# MinipHV0_1.net
KiCad netlist of a schematic drawn in EAGLE
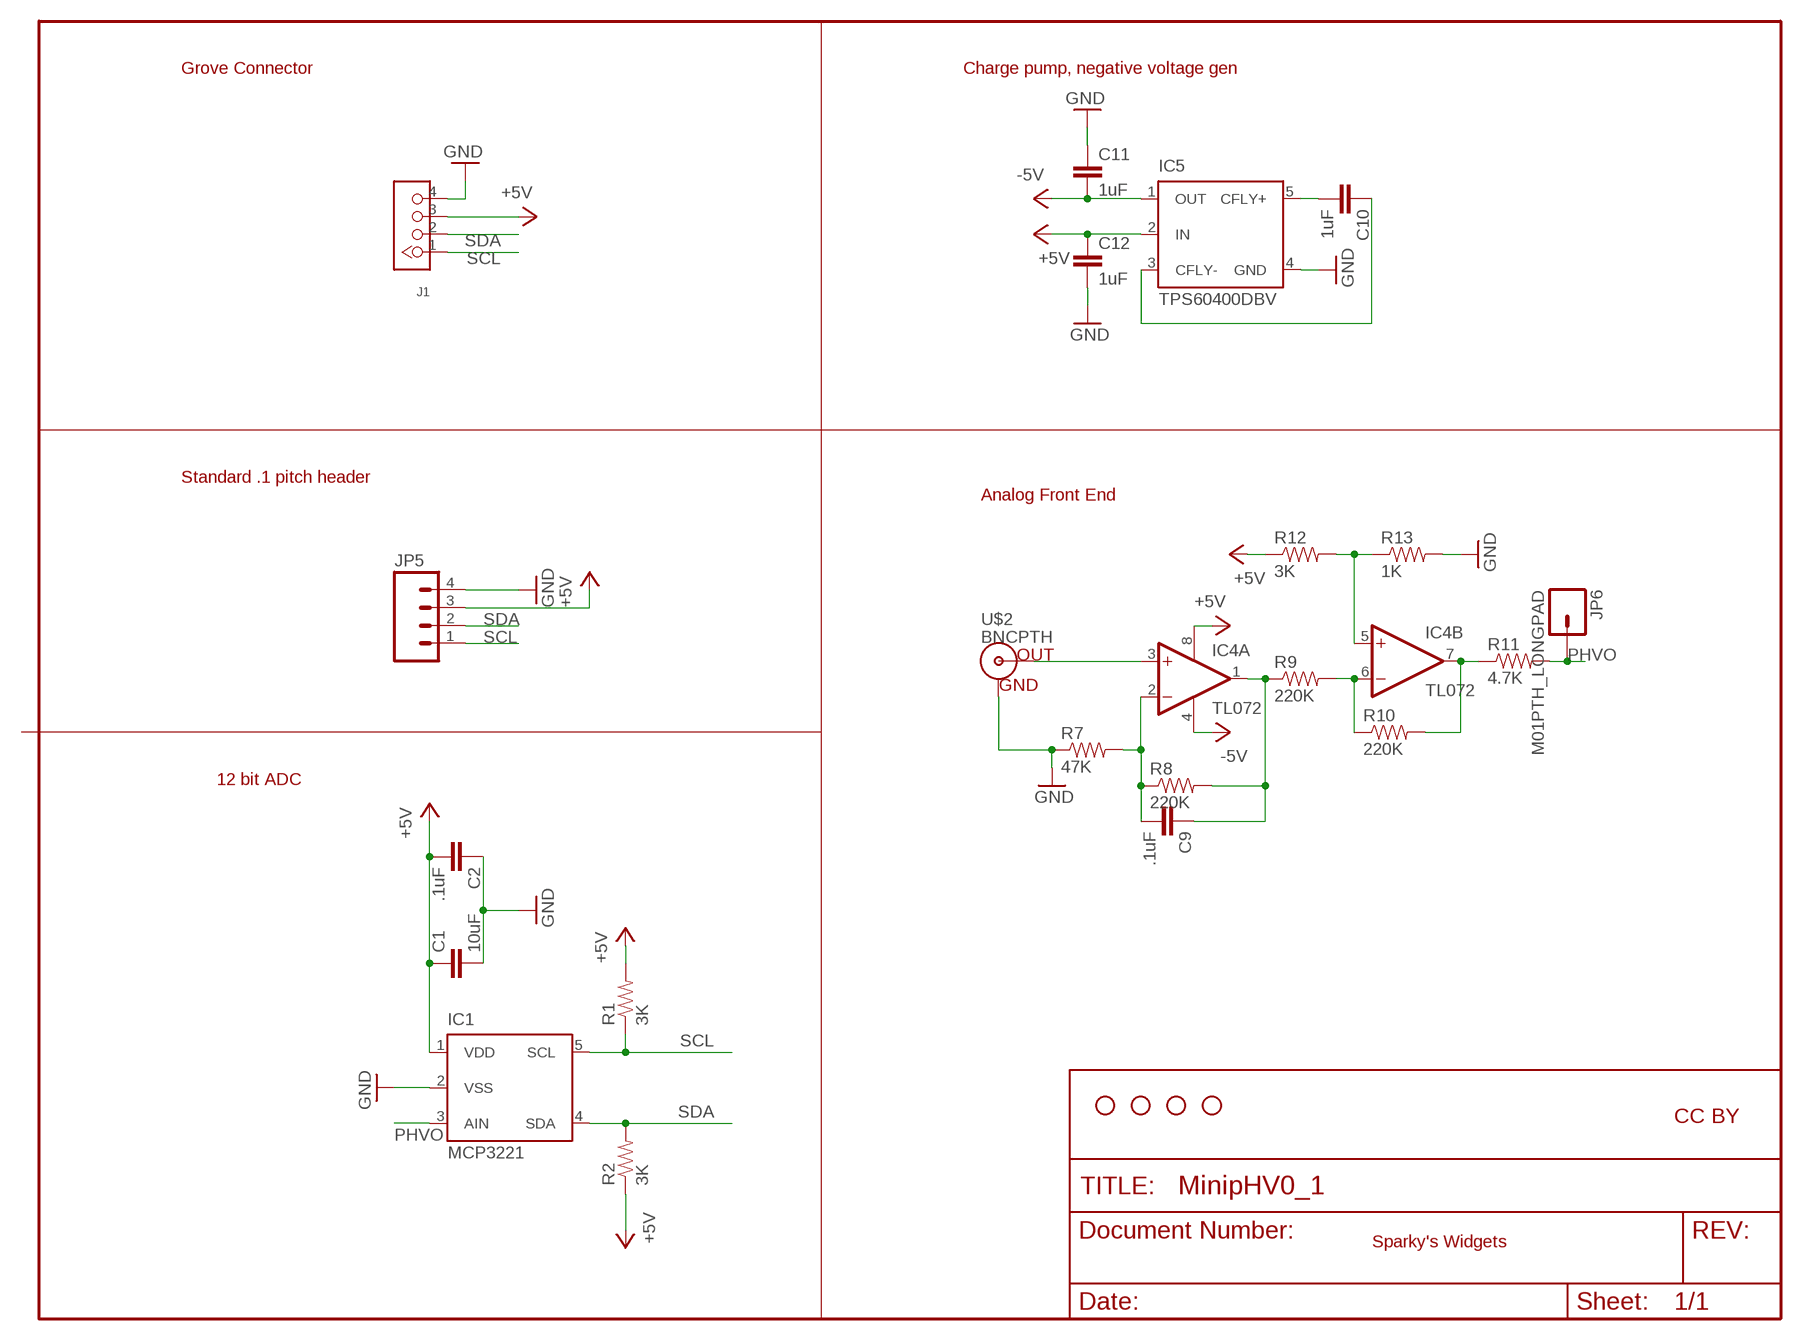
[diagram p0: schematic, sheet 1]

(export (version "E")
  (design (tool "Eeschema 10.0.6"))
  (components
    (comp (ref "C1")
      (value "10uF")
      (footprint "eagle-import:0805")
      (libsource (lib "eagle-import") (part "CAP0805"))
    )
    (comp (ref "C2")
      (value ".1uF")
      (footprint "eagle-import:0805")
      (libsource (lib "eagle-import") (part "CAP0805"))
    )
    (comp (ref "C9")
      (value ".1uF")
      (footprint "eagle-import:0805")
      (libsource (lib "eagle-import") (part "CAP0805"))
    )
    (comp (ref "C10")
      (value "1uF")
      (footprint "eagle-import:0805")
      (libsource (lib "eagle-import") (part "CAP0805"))
    )
    (comp (ref "C11")
      (value "1uF")
      (footprint "eagle-import:0805")
      (libsource (lib "eagle-import") (part "CAP0805"))
    )
    (comp (ref "C12")
      (value "1uF")
      (footprint "eagle-import:0805")
      (libsource (lib "eagle-import") (part "CAP0805"))
    )
    (comp (ref "IC1")
      (value "MCP3221")
      (footprint "eagle-import:SOT23-DBV")
      (libsource (lib "eagle-import") (part "MCP3221"))
    )
    (comp (ref "IC4")
      (value "TL072")
      (footprint "eagle-import:SO08")
      (libsource (lib "eagle-import") (part "LM358D"))
    )
    (comp (ref "IC5")
      (value "TPS60400DBV")
      (footprint "eagle-import:SOT23-DBV")
      (libsource (lib "eagle-import") (part "TPS60400DBV"))
    )
    (comp (ref "J1")
      (value "TWIG-4P-2.0-2.0")
      (footprint "eagle-import:4P-2.0")
      (libsource (lib "eagle-import") (part "TWIG-4P-2.0-2.0"))
    )
    (comp (ref "JP1")
      (value "STAND-OFF")
      (footprint "eagle-import:STAND-OFF")
      (libsource (lib "eagle-import") (part "STAND-OFF"))
    )
    (comp (ref "JP2")
      (value "STAND-OFF")
      (footprint "eagle-import:STAND-OFF")
      (libsource (lib "eagle-import") (part "STAND-OFF"))
    )
    (comp (ref "JP3")
      (value "STAND-OFF")
      (footprint "eagle-import:STAND-OFF")
      (libsource (lib "eagle-import") (part "STAND-OFF"))
    )
    (comp (ref "JP4")
      (value "STAND-OFF")
      (footprint "eagle-import:STAND-OFF")
      (libsource (lib "eagle-import") (part "STAND-OFF"))
    )
    (comp (ref "JP5")
      (value "M04PTH")
      (footprint "eagle-import:1X04")
      (libsource (lib "eagle-import") (part "M04PTH"))
    )
    (comp (ref "JP6")
      (value "M01PTH_LONGPAD")
      (footprint "eagle-import:1X01_LONGPAD")
      (libsource (lib "eagle-import") (part "M01PTH_LONGPAD"))
    )
    (comp (ref "R1")
      (value "3K")
      (footprint "eagle-import:0805")
      (libsource (lib "eagle-import") (part "RESISTOR0805-RES"))
    )
    (comp (ref "R2")
      (value "3K")
      (footprint "eagle-import:0805")
      (libsource (lib "eagle-import") (part "RESISTOR0805-RES"))
    )
    (comp (ref "R7")
      (value "47K")
      (footprint "eagle-import:0805")
      (libsource (lib "eagle-import") (part "RESISTOR0805-RES"))
    )
    (comp (ref "R8")
      (value "220K")
      (footprint "eagle-import:0805")
      (libsource (lib "eagle-import") (part "RESISTOR0805-RES"))
    )
    (comp (ref "R9")
      (value "220K")
      (footprint "eagle-import:0805")
      (libsource (lib "eagle-import") (part "RESISTOR0805-RES"))
    )
    (comp (ref "R10")
      (value "220K")
      (footprint "eagle-import:0805")
      (libsource (lib "eagle-import") (part "RESISTOR0805-RES"))
    )
    (comp (ref "R11")
      (value "4.7K")
      (footprint "eagle-import:0805")
      (libsource (lib "eagle-import") (part "RESISTOR0805-RES"))
    )
    (comp (ref "R12")
      (value "3K")
      (footprint "eagle-import:0805")
      (libsource (lib "eagle-import") (part "RESISTOR0805-RES"))
    )
    (comp (ref "R13")
      (value "1K")
      (footprint "eagle-import:0805")
      (libsource (lib "eagle-import") (part "RESISTOR0805-RES"))
    )
    (comp (ref "U$2")
      (value "BNCPTH")
      (footprint "eagle-import:BNC")
      (libsource (lib "eagle-import") (part "BNCPTH"))
    )
  )
  (nets
    (net (code "1") (name "+5V") (class "Default")
      (node (ref "C1") (pin "1") (pinfunction "1_1") (pintype "passive"))
      (node (ref "C12") (pin "1") (pinfunction "1_1") (pintype "passive"))
      (node (ref "C2") (pin "2") (pinfunction "2_2") (pintype "passive"))
      (node (ref "IC1") (pin "1") (pinfunction "VDD_1") (pintype "power_in"))
      (node (ref "IC4") (pin "8") (pinfunction "V+_8") (pintype "power_in"))
      (node (ref "IC5") (pin "2") (pinfunction "IN_2") (pintype "input"))
      (node (ref "J1") (pin "3") (pinfunction "3_3") (pintype "bidirectional"))
      (node (ref "JP5") (pin "3") (pinfunction "3_3") (pintype "passive"))
      (node (ref "R1") (pin "2") (pinfunction "2_2") (pintype "passive"))
      (node (ref "R12") (pin "1") (pinfunction "1_1") (pintype "passive"))
      (node (ref "R2") (pin "1") (pinfunction "1_1") (pintype "passive"))
    )
    (net (code "2") (name "-5V") (class "Default")
      (node (ref "C11") (pin "2") (pinfunction "2_2") (pintype "passive"))
      (node (ref "IC4") (pin "4") (pinfunction "V-_4") (pintype "power_in"))
      (node (ref "IC5") (pin "1") (pinfunction "OUT_1") (pintype "input"))
    )
    (net (code "3") (name "/PHVO") (class "Default")
      (node (ref "IC1") (pin "3") (pinfunction "AIN_3") (pintype "input"))
      (node (ref "JP6") (pin "1") (pinfunction "1_1") (pintype "passive"))
      (node (ref "R11") (pin "2") (pinfunction "2_2") (pintype "passive"))
    )
    (net (code "4") (name "/SCL") (class "Default")
      (node (ref "IC1") (pin "5") (pinfunction "SCL_5") (pintype "bidirectional"))
      (node (ref "J1") (pin "1") (pinfunction "1_1") (pintype "bidirectional"))
      (node (ref "JP5") (pin "1") (pinfunction "1_1") (pintype "passive"))
      (node (ref "R1") (pin "1") (pinfunction "1_1") (pintype "passive"))
    )
    (net (code "5") (name "/SDA") (class "Default")
      (node (ref "IC1") (pin "4") (pinfunction "SDA_4") (pintype "bidirectional"))
      (node (ref "J1") (pin "2") (pinfunction "2_2") (pintype "bidirectional"))
      (node (ref "JP5") (pin "2") (pinfunction "2_2") (pintype "passive"))
      (node (ref "R2") (pin "2") (pinfunction "2_2") (pintype "passive"))
    )
    (net (code "6") (name "GND") (class "Default")
      (node (ref "C1") (pin "2") (pinfunction "2_2") (pintype "passive"))
      (node (ref "C11") (pin "1") (pinfunction "1_1") (pintype "passive"))
      (node (ref "C12") (pin "2") (pinfunction "2_2") (pintype "passive"))
      (node (ref "C2") (pin "1") (pinfunction "1_1") (pintype "passive"))
      (node (ref "IC1") (pin "2") (pinfunction "VSS_2") (pintype "power_in"))
      (node (ref "IC5") (pin "4") (pinfunction "GND_4") (pintype "passive"))
      (node (ref "J1") (pin "4") (pinfunction "4_4") (pintype "bidirectional"))
      (node (ref "JP5") (pin "4") (pinfunction "4_4") (pintype "passive"))
      (node (ref "R13") (pin "2") (pinfunction "2_2") (pintype "passive"))
      (node (ref "R7") (pin "1") (pinfunction "1_1") (pintype "passive"))
      (node (ref "U$2") (pin "GND") (pinfunction "GND_GND") (pintype "bidirectional"))
    )
    (net (code "7") (name "Net-(IC4A-+IN)") (class "Default")
      (node (ref "IC4") (pin "3") (pinfunction "+IN_3") (pintype "input"))
      (node (ref "U$2") (pin "S") (pinfunction "OUT_S") (pintype "bidirectional"))
    )
    (net (code "8") (name "Net-(IC4A--IN)") (class "Default")
      (node (ref "C9") (pin "2") (pinfunction "2_2") (pintype "passive"))
      (node (ref "IC4") (pin "2") (pinfunction "-IN_2") (pintype "input"))
      (node (ref "R7") (pin "2") (pinfunction "2_2") (pintype "passive"))
      (node (ref "R8") (pin "1") (pinfunction "1_1") (pintype "passive"))
    )
    (net (code "9") (name "Net-(IC4A-OUT)") (class "Default")
      (node (ref "C9") (pin "1") (pinfunction "1_1") (pintype "passive"))
      (node (ref "IC4") (pin "1") (pinfunction "OUT_1") (pintype "output"))
      (node (ref "R8") (pin "2") (pinfunction "2_2") (pintype "passive"))
      (node (ref "R9") (pin "1") (pinfunction "1_1") (pintype "passive"))
    )
    (net (code "10") (name "Net-(IC4B-+IN)") (class "Default")
      (node (ref "IC4") (pin "5") (pinfunction "+IN_5") (pintype "input"))
      (node (ref "R12") (pin "2") (pinfunction "2_2") (pintype "passive"))
      (node (ref "R13") (pin "1") (pinfunction "1_1") (pintype "passive"))
    )
    (net (code "11") (name "Net-(IC4B--IN)") (class "Default")
      (node (ref "IC4") (pin "6") (pinfunction "-IN_6") (pintype "input"))
      (node (ref "R10") (pin "1") (pinfunction "1_1") (pintype "passive"))
      (node (ref "R9") (pin "2") (pinfunction "2_2") (pintype "passive"))
    )
    (net (code "12") (name "Net-(IC4B-OUT)") (class "Default")
      (node (ref "IC4") (pin "7") (pinfunction "OUT_7") (pintype "output"))
      (node (ref "R10") (pin "2") (pinfunction "2_2") (pintype "passive"))
      (node (ref "R11") (pin "1") (pinfunction "1_1") (pintype "passive"))
    )
    (net (code "13") (name "Net-(IC5-CFLY+)") (class "Default")
      (node (ref "C10") (pin "2") (pinfunction "2_2") (pintype "passive"))
      (node (ref "IC5") (pin "5") (pinfunction "CFLY+_5") (pintype "passive"))
    )
    (net (code "14") (name "Net-(IC5-CFLY-)") (class "Default")
      (node (ref "C10") (pin "1") (pinfunction "1_1") (pintype "passive"))
      (node (ref "IC5") (pin "3") (pinfunction "CFLY-_3") (pintype "power_in"))
    )
  )
)
